# board2.net
KiCad netlist of a schematic drawn in Altium Designer
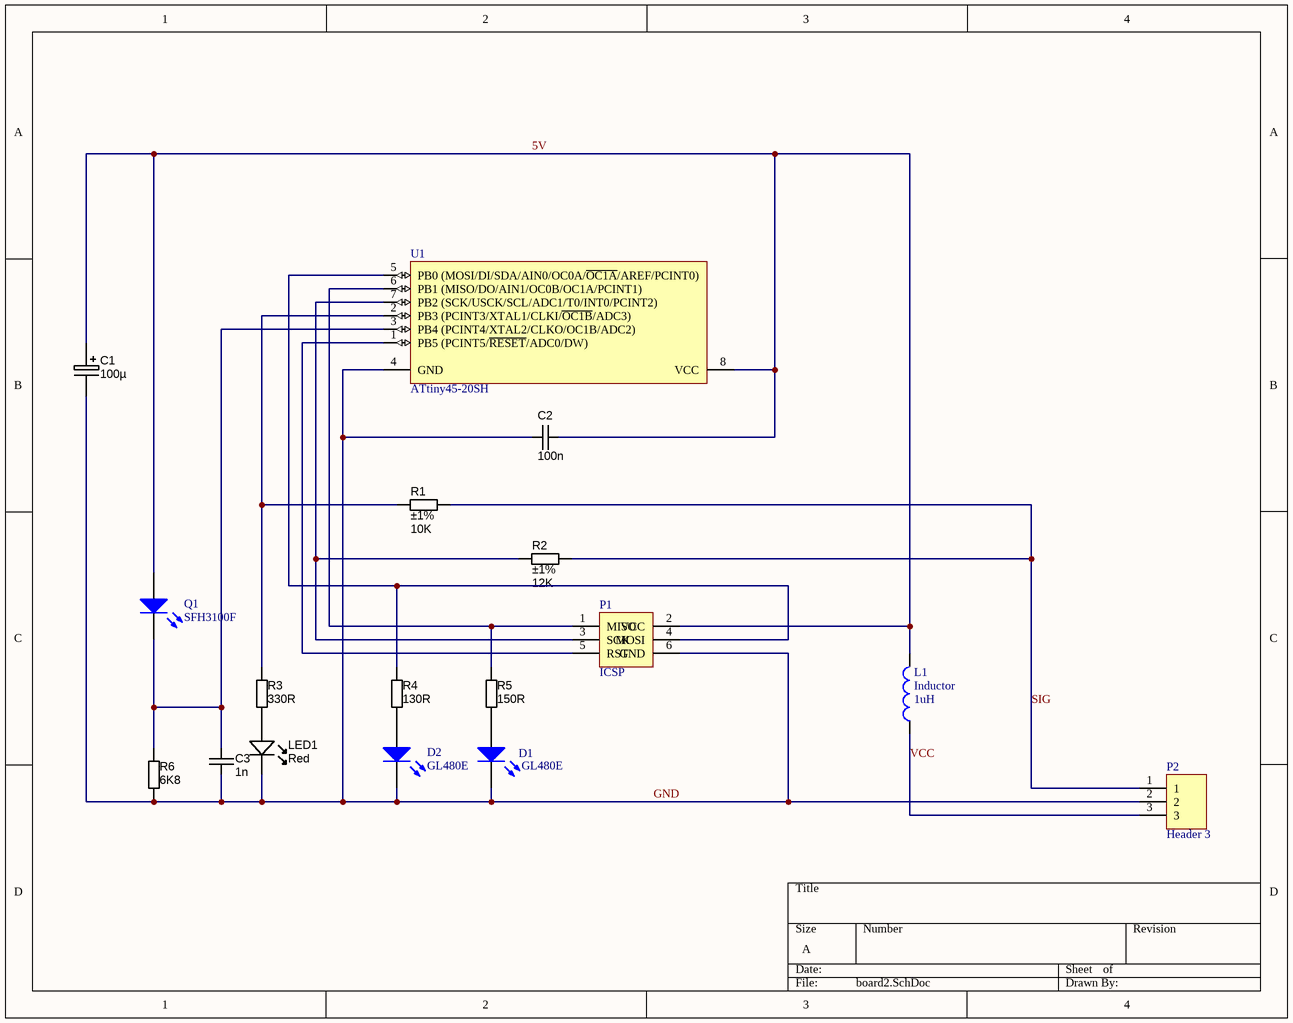
[diagram p0: board2.SchDoc]

(export (version "E")
  (design (tool "Eeschema 10.0.6"))
  (components
    (comp (ref "C1")
      (value "100µ")
      (footprint "CAPAE200P550X1200_FLAT2")
      (description "Capacitor THD Electrolytic 100uF 20% 16V Radial")
      (fields (field (name "TOLERANCE") "±20%") (field (name "MANUFACTURER") "Panasonic - ECG"))
      (libsource (lib "PBL - Capacitors") (part "CAPE_100u_16V_THD"))
    )
    (comp (ref "C2")
      (value "100n")
      (footprint "CAPC1005X55N")
      (description "Capacitor SMD Cer 100nF 10% 16V X5R 0402")
      (fields (field (name "TOLERANCE") "±10%"))
      (libsource (lib "PBL - Capacitors") (part "CAPC_100n_0402_X5R_16V_10%"))
    )
    (comp (ref "C3")
      (value "1n")
      (footprint "CAPC1005X55N")
      (description "Capacitor SMD Cer 1nF 10% 16V X7R 0402")
      (fields (field (name "TOLERANCE") "±10%"))
      (libsource (lib "PBL - Capacitors") (part "CAPC_1n_0402_X7R_16V_10%"))
    )
    (comp (ref "D1")
      (value "GL480E")
      (footprint "LED-0")
      (description "Typical INFRARED GaAs LED")
      (fields (field (name "PUBLISHER") "Altium Limited"))
      (libsource (lib "Miscellaneous Devices") (part "LED0"))
    )
    (comp (ref "D2")
      (value "GL480E")
      (footprint "LED-0")
      (description "Typical INFRARED GaAs LED")
      (fields (field (name "PUBLISHER") "Altium Limited"))
      (libsource (lib "Miscellaneous Devices") (part "LED0"))
    )
    (comp (ref "L1")
      (value "Inductor")
      (footprint "0402-A")
      (fields (field (name "ALTIUM_VALUE") "1uH") (field (name "PUBLISHER") "Altium Limited"))
      (libsource (lib "Miscellaneous Devices") (part "Inductor"))
    )
    (comp (ref "LED1")
      (value "Red")
      (footprint "LED-0603-RED")
      (description "LED 0603 SMD Hyper Red 630nm 220mcd 20mA")
      (libsource (lib "PBL - Light Sources") (part "LED_SMD_Red_0603_220mcd"))
    )
    (comp (ref "P1")
      (value "ICSP")
      (footprint "HDR2X3")
      (description "Header, 3-Pin, Dual row")
      (fields (field (name "PUBLISHER") "Altium Limited"))
      (libsource (lib "Miscellaneous Connectors") (part "Header 3X2"))
    )
    (comp (ref "P2")
      (value "Header 3")
      (footprint "HDR1X3")
      (description "Header, 3-Pin")
      (fields (field (name "PUBLISHER") "Altium Limited"))
      (libsource (lib "Miscellaneous Connectors") (part "Header 3"))
    )
    (comp (ref "Q1")
      (value "SFH3100F")
      (footprint "LED-0")
      (description "IR Phototransistor")
      (fields (field (name "PUBLISHER") "Altium Limited"))
      (libsource (lib "Miscellaneous Devices") (part "LED0"))
    )
    (comp (ref "R1")
      (value "10K")
      (footprint "RESC1005X40N")
      (description "Resistor SMD chip 10k Ohm 0.063W 1% 0402")
      (fields (field (name "TOLERANCE") "±1%") (field (name "Comment") "Thick Film"))
      (libsource (lib "PBL - Resistors") (part "RES_10K_0402_1%"))
    )
    (comp (ref "R2")
      (value "12K")
      (footprint "RESC1005X40N")
      (description "Resistor SMD chip 10k Ohm 0.063W 1% 0402")
      (fields (field (name "TOLERANCE") "±1%") (field (name "Comment") "Thick Film"))
      (libsource (lib "PBL - Resistors") (part "RES_10K_0402_1%"))
    )
    (comp (ref "R3")
      (value "330R")
      (footprint "RESC1608X55N")
      (description "Resistor SMD chip 330 Ohm 0.1W 5% 0603")
      (fields (field (name "TOLERANCE") "±5%") (field (name "Comment") "Thick Film"))
      (libsource (lib "PBL - Resistors") (part "RES_330R_0603_5%"))
    )
    (comp (ref "R4")
      (value "130R")
      (footprint "RESC1608X55N")
      (description "Resistor SMD chip 2.2k Ohm 0.1W 5% 0603")
      (fields (field (name "TOLERANCE") "±5%") (field (name "Comment") "Thick Film"))
      (libsource (lib "PBL - Resistors") (part "RES_2K2_0603_5%"))
    )
    (comp (ref "R5")
      (value "150R")
      (footprint "RESC1608X55N")
      (description "Resistor SMD chip 2.2k Ohm 0.1W 5% 0603")
      (fields (field (name "TOLERANCE") "±5%") (field (name "Comment") "Thick Film"))
      (libsource (lib "PBL - Resistors") (part "RES_2K2_0603_5%"))
    )
    (comp (ref "R6")
      (value "6K8")
      (footprint "RESC1608X55N")
      (description "Resistor SMD chip 2.2k Ohm 0.1W 5% 0603")
      (fields (field (name "TOLERANCE") "±5%") (field (name "Comment") "Thick Film"))
      (libsource (lib "PBL - Resistors") (part "RES_2K2_0603_5%"))
    )
    (comp (ref "U1")
      (value "ATtiny45-20SH")
      (footprint "8S2_N")
      (libsource (lib "Atmel Microcontroller tinyAVR") (part "ATtiny45-20SH"))
    )
  )
  (nets
    (net (code "1") (name "/5V") (class "Default")
      (node (ref "C1") (pin "1") (pintype "passive"))
      (node (ref "C2") (pin "2") (pintype "passive"))
      (node (ref "L1") (pin "2") (pinfunction "2_2") (pintype "passive"))
      (node (ref "P1") (pin "2") (pinfunction "VCC_2") (pintype "passive"))
      (node (ref "Q1") (pin "1") (pinfunction "A_1") (pintype "passive"))
      (node (ref "U1") (pin "8") (pinfunction "VCC_8") (pintype "power_in"))
    )
    (net (code "2") (name "/GND") (class "Default")
      (node (ref "C1") (pin "2") (pintype "passive"))
      (node (ref "C2") (pin "1") (pintype "passive"))
      (node (ref "C3") (pin "2") (pintype "passive"))
      (node (ref "D1") (pin "2") (pinfunction "K_2") (pintype "passive"))
      (node (ref "D2") (pin "2") (pinfunction "K_2") (pintype "passive"))
      (node (ref "LED1") (pin "K") (pinfunction "K_K") (pintype "passive"))
      (node (ref "P1") (pin "6") (pinfunction "GND_6") (pintype "passive"))
      (node (ref "P2") (pin "2") (pinfunction "2_2") (pintype "passive"))
      (node (ref "R6") (pin "1") (pinfunction "1_1") (pintype "passive"))
      (node (ref "U1") (pin "4") (pinfunction "GND_4") (pintype "power_in"))
    )
    (net (code "3") (name "/SIG") (class "Default")
      (node (ref "P2") (pin "1") (pinfunction "1_1") (pintype "passive"))
      (node (ref "R1") (pin "2") (pinfunction "2_2") (pintype "passive"))
      (node (ref "R2") (pin "2") (pinfunction "2_2") (pintype "passive"))
    )
    (net (code "4") (name "/VCC") (class "Default")
      (node (ref "L1") (pin "1") (pinfunction "1_1") (pintype "passive"))
      (node (ref "P2") (pin "3") (pinfunction "3_3") (pintype "passive"))
    )
    (net (code "5") (name "Net-(D1-A)") (class "Default")
      (node (ref "D1") (pin "1") (pinfunction "A_1") (pintype "passive"))
      (node (ref "R5") (pin "1") (pinfunction "1_1") (pintype "passive"))
    )
    (net (code "6") (name "Net-(D2-A)") (class "Default")
      (node (ref "D2") (pin "1") (pinfunction "A_1") (pintype "passive"))
      (node (ref "R4") (pin "1") (pinfunction "1_1") (pintype "passive"))
    )
    (net (code "7") (name "Net-(LED1-PadA)") (class "Default")
      (node (ref "LED1") (pin "A") (pinfunction "A_A") (pintype "passive"))
      (node (ref "R3") (pin "2") (pinfunction "2_2") (pintype "passive"))
    )
    (net (code "8") (name "Net-(P1-MISO)") (class "Default")
      (node (ref "P1") (pin "1") (pinfunction "MISO_1") (pintype "passive"))
      (node (ref "R5") (pin "2") (pinfunction "2_2") (pintype "passive"))
      (node (ref "U1") (pin "6") (pinfunction "PB1_(MISO/DO/AIN1/OC0B/OC1A/PCINT1)_6") (pintype "bidirectional"))
    )
    (net (code "9") (name "Net-(P1-MOSI)") (class "Default")
      (node (ref "P1") (pin "4") (pinfunction "MOSI_4") (pintype "passive"))
      (node (ref "R4") (pin "2") (pinfunction "2_2") (pintype "passive"))
      (node (ref "U1") (pin "5") (pinfunction "PB0_(MOSI/DI/SDA/AIN0/OC0A/~{OC1A}/AREF/PCINT0)_5") (pintype "bidirectional"))
    )
    (net (code "10") (name "Net-(P1-RST)") (class "Default")
      (node (ref "P1") (pin "5") (pinfunction "RST_5") (pintype "passive"))
      (node (ref "U1") (pin "1") (pinfunction "PB5_(PCINT5/~{RESET}/ADC0/DW)_1") (pintype "bidirectional"))
    )
    (net (code "11") (name "Net-(P1-SCK)") (class "Default")
      (node (ref "P1") (pin "3") (pinfunction "SCK_3") (pintype "passive"))
      (node (ref "R2") (pin "1") (pinfunction "1_1") (pintype "passive"))
      (node (ref "U1") (pin "7") (pinfunction "PB2_(SCK/USCK/SCL/ADC1/T0/INT0/PCINT2)_7") (pintype "bidirectional"))
    )
    (net (code "12") (name "Net-(Q1-K)") (class "Default")
      (node (ref "C3") (pin "1") (pintype "passive"))
      (node (ref "Q1") (pin "2") (pinfunction "K_2") (pintype "passive"))
      (node (ref "R6") (pin "2") (pinfunction "2_2") (pintype "passive"))
      (node (ref "U1") (pin "3") (pinfunction "PB4_(PCINT4/XTAL2/CLKO/OC1B/ADC2)_3") (pintype "bidirectional"))
    )
    (net (code "13") (name "Net-(U1-PB3_(PCINT3{slash}XTAL1{slash}CLKI{slash}~{OC1B}{slash}ADC3))") (class "Default")
      (node (ref "R1") (pin "1") (pinfunction "1_1") (pintype "passive"))
      (node (ref "R3") (pin "1") (pinfunction "1_1") (pintype "passive"))
      (node (ref "U1") (pin "2") (pinfunction "PB3_(PCINT3/XTAL1/CLKI/~{OC1B}/ADC3)_2") (pintype "bidirectional"))
    )
  )
)
